# ReflowOwen.net
KiCad netlist of a schematic drawn in Altium Designer
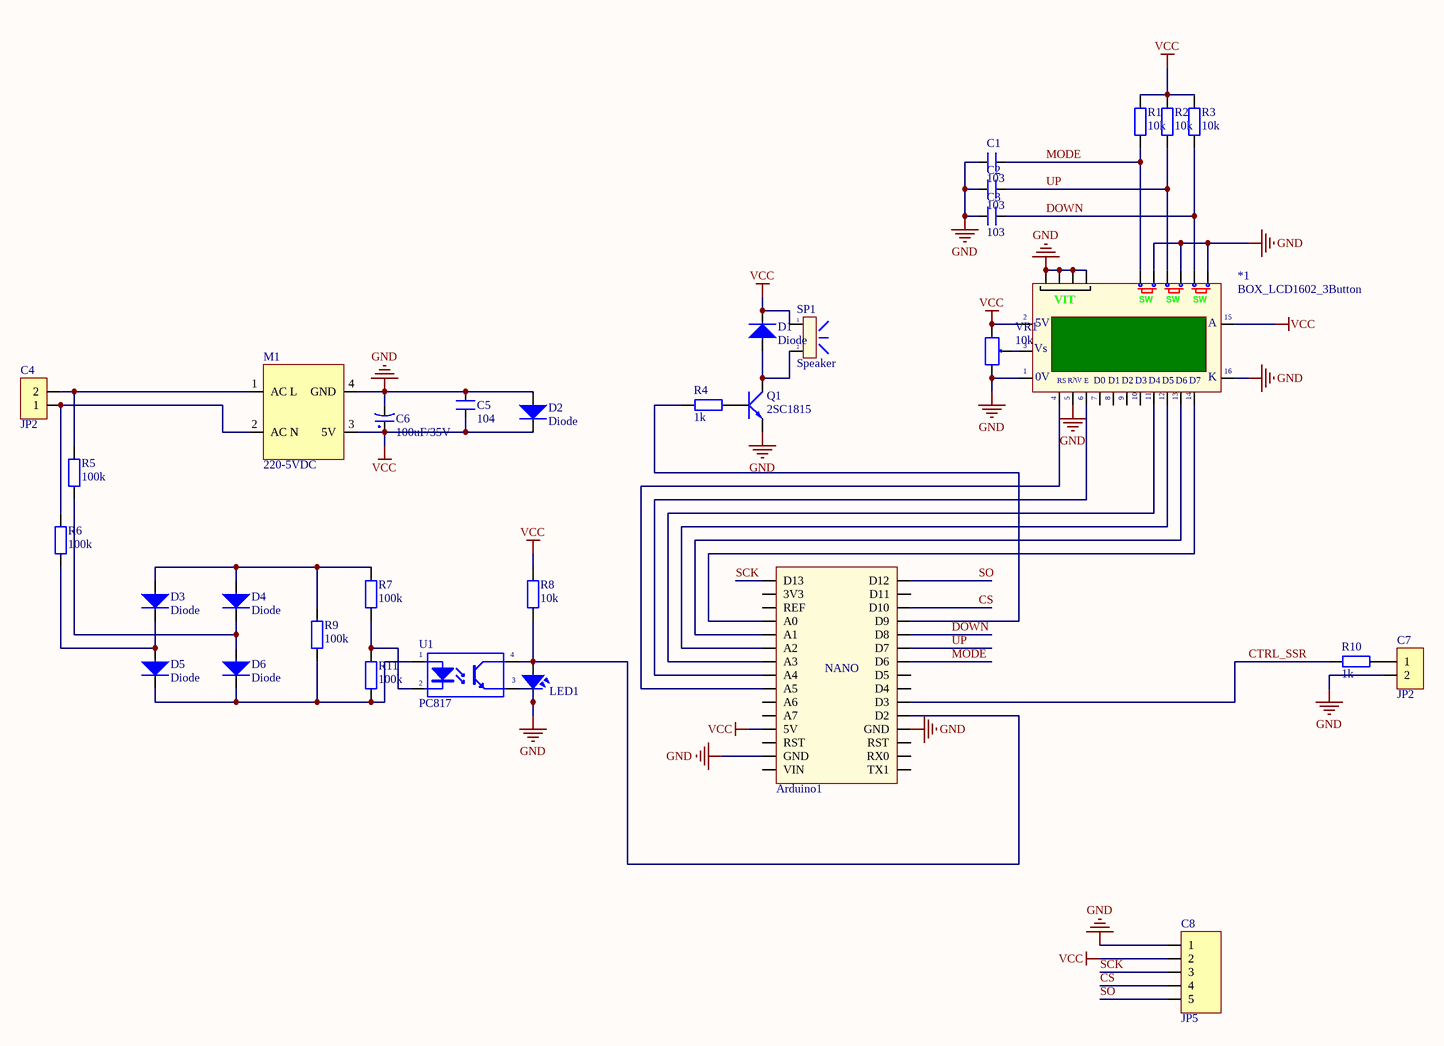
[diagram p0: ReflowOwen.SchDoc]

(export (version "E")
  (design (tool "Eeschema 10.0.6"))
  (components
    (comp (ref "*1")
      (value "BOX_LCD1602_3Button")
      (footprint "BOX_LCD1602_3Button")
      (libsource (lib "OBIT_TESLA") (part "BOX_LCD1602_3Button"))
    )
    (comp (ref "Arduino1")
      (value "Arduino Nano")
      (footprint "Arduino Nano")
      (description "Arduino NANO")
      (libsource (lib "Tesla_Thinh") (part "Arduino Nano"))
    )
    (comp (ref "C1")
      (value "103")
      (footprint "SM-0805")
      (description "Cap SMD")
      (libsource (lib "OBIT_TESLA") (part "CM"))
    )
    (comp (ref "C2")
      (value "103")
      (footprint "SM-0805")
      (description "Cap SMD")
      (libsource (lib "OBIT_TESLA") (part "CM"))
    )
    (comp (ref "C3")
      (value "103")
      (footprint "SM-0805")
      (description "Cap SMD")
      (libsource (lib "OBIT_TESLA") (part "CM"))
    )
    (comp (ref "C4")
      (value "JP2")
      (footprint "JP2-C1T")
      (description "WR-PHD 2.54 mm Angled Socket Header")
      (fields
        (field (name "MANUFACTURER") "Würth Elektronik eiSos GmbH")
        (field (name "PARTNO") "613002143121")
        (field (name "CREATED BY") "Karrer Zheng")
      )
      (libsource (lib "OBIT_TESLA") (part "JP2"))
    )
    (comp (ref "C5")
      (value "104")
      (footprint "CN2")
      (description "Cap np 104 => 105pF")
      (libsource (lib "OBIT_TESLA") (part "CN2"))
    )
    (comp (ref "C6")
      (value "100uF/35V")
      (footprint "CP1.5/3.4")
      (description "Cap 100uF/35V - 470uF/16V")
      (libsource (lib "OBIT_TESLA") (part "CP3"))
    )
    (comp (ref "C7")
      (value "JP2")
      (footprint "JP2-C1T")
      (description "WR-PHD 2.54 mm Angled Socket Header")
      (fields
        (field (name "MANUFACTURER") "Würth Elektronik eiSos GmbH")
        (field (name "PARTNO") "613002143121")
        (field (name "CREATED BY") "Karrer Zheng")
      )
      (libsource (lib "") (part "JP2_1"))
    )
    (comp (ref "C8")
      (value "JP5")
      (footprint "JP5-C1T")
      (description "WR-PHD 2.54 mm Angled Socket Header")
      (fields
        (field (name "MANUFACTURER") "Würth Elektronik eiSos GmbH")
        (field (name "PARTNO") "613005143121")
        (field (name "CREATED BY") "Karrer Zheng")
      )
      (libsource (lib "OBIT_TESLA") (part "JP5"))
    )
    (comp (ref "D1") (value "Diode") (footprint "DIO-SMD-106") (libsource (lib "OBIT_TESLA") (part "Diode")))
    (comp (ref "D2") (value "Diode") (footprint "DIO-SMD-106") (libsource (lib "OBIT_TESLA") (part "Diode")))
    (comp (ref "D3") (value "Diode") (footprint "D1A") (libsource (lib "OBIT_TESLA") (part "Diode")))
    (comp (ref "D4") (value "Diode") (footprint "D1A") (libsource (lib "OBIT_TESLA") (part "Diode")))
    (comp (ref "D5") (value "Diode") (footprint "D1A") (libsource (lib "OBIT_TESLA") (part "Diode")))
    (comp (ref "D6") (value "Diode") (footprint "D1A") (libsource (lib "OBIT_TESLA") (part "Diode")))
    (comp (ref "LED1")
      (value "LED")
      (footprint "LED-5-BLUE")
      (description "LED Single colour Green and Red")
      (libsource (lib "Tesla_Thinh") (part "LED"))
    )
    (comp (ref "M1")
      (value "220-5VDC")
      (footprint "5V 700mA 3.5W AC DC")
      (libsource (lib "OBIT_TESLA") (part "5V 700mA 3.5W AC 220 to DC"))
    )
    (comp (ref "Q1")
      (value "2SC1815")
      (footprint "TO92-123")
      (description "NPN 600mW, ECB")
      (libsource (lib "OBIT_TESLA") (part "2SC1815"))
    )
    (comp (ref "R1")
      (value "10k")
      (footprint "RES-1/4W")
      (description "Resistor R1/4W")
      (libsource (lib "OBIT_TESLA") (part "R"))
    )
    (comp (ref "R2")
      (value "10k")
      (footprint "RES-1/4W")
      (description "Resistor R1/4W")
      (libsource (lib "OBIT_TESLA") (part "R"))
    )
    (comp (ref "R3")
      (value "10k")
      (footprint "RES-1/4W")
      (description "Resistor R1/4W")
      (libsource (lib "OBIT_TESLA") (part "R"))
    )
    (comp (ref "R4")
      (value "1k")
      (footprint "RES-1/4W")
      (description "Resistor R1/4W")
      (libsource (lib "OBIT_TESLA") (part "R"))
    )
    (comp (ref "R5")
      (value "100k")
      (footprint "RES-1/4W")
      (description "Resistor R1/4W")
      (libsource (lib "OBIT_TESLA") (part "R"))
    )
    (comp (ref "R6")
      (value "100k")
      (footprint "RES-1/4W")
      (description "Resistor R1/4W")
      (libsource (lib "OBIT_TESLA") (part "R"))
    )
    (comp (ref "R7")
      (value "100k")
      (footprint "RES-1/4W")
      (description "Resistor R1/4W")
      (libsource (lib "OBIT_TESLA") (part "R"))
    )
    (comp (ref "R8")
      (value "10k")
      (footprint "RES-1/4W")
      (description "Resistor R1/4W")
      (libsource (lib "OBIT_TESLA") (part "R"))
    )
    (comp (ref "R9")
      (value "100k")
      (footprint "RES-1/4W")
      (description "Resistor R1/4W")
      (libsource (lib "OBIT_TESLA") (part "R"))
    )
    (comp (ref "R10")
      (value "1k")
      (footprint "RES-1/4W")
      (description "Resistor R1/4W")
      (libsource (lib "OBIT_TESLA") (part "R"))
    )
    (comp (ref "R11")
      (value "100k")
      (footprint "RES-1/4W")
      (description "Resistor R1/4W")
      (libsource (lib "OBIT_TESLA") (part "R"))
    )
    (comp (ref "SP1")
      (value "Speaker")
      (footprint "SPK")
      (description "Speaker Chip")
      (libsource (lib "OBIT_TESLA") (part "SPK"))
    )
    (comp (ref "U1")
      (value "PC817")
      (footprint "DIP4")
      (description "Single Opto")
      (libsource (lib "Tesla_Thinh") (part "PC817"))
    )
    (comp (ref "VR1") (value "10k") (footprint "VR-S2") (libsource (lib "OBIT_TESLA") (part "Resistor Var")))
  )
  (nets
    (net (code "1") (name "/CS") (class "Default")
      (node (ref "Arduino1") (pin "D10") (pinfunction "D10_D10") (pintype "passive"))
      (node (ref "C8") (pin "4") (pinfunction "4_4") (pintype "passive"))
    )
    (net (code "2") (name "/CTRL_SSR") (class "Default")
      (node (ref "Arduino1") (pin "D3") (pinfunction "D3_D3") (pintype "passive"))
      (node (ref "R10") (pin "1") (pinfunction "1_1") (pintype "passive"))
    )
    (net (code "3") (name "/DOWN") (class "Default")
      (node (ref "*1") (pin "21") (pinfunction "21_21") (pintype "passive"))
      (node (ref "Arduino1") (pin "D8") (pinfunction "D8_D8") (pintype "passive"))
      (node (ref "C3") (pin "2") (pinfunction "2_2") (pintype "passive"))
      (node (ref "R3") (pin "1") (pinfunction "1_1") (pintype "passive"))
    )
    (net (code "4") (name "/MODE") (class "Default")
      (node (ref "*1") (pin "17") (pinfunction "17_17") (pintype "passive"))
      (node (ref "Arduino1") (pin "D6") (pinfunction "D6_D6") (pintype "passive"))
      (node (ref "C1") (pin "2") (pinfunction "2_2") (pintype "passive"))
      (node (ref "R1") (pin "1") (pinfunction "1_1") (pintype "passive"))
    )
    (net (code "5") (name "/SCK") (class "Default")
      (node (ref "Arduino1") (pin "D13") (pinfunction "D13_D13") (pintype "passive"))
      (node (ref "C8") (pin "3") (pinfunction "3_3") (pintype "passive"))
    )
    (net (code "6") (name "/SO") (class "Default")
      (node (ref "Arduino1") (pin "D12") (pinfunction "D12_D12") (pintype "passive"))
      (node (ref "C8") (pin "5") (pinfunction "5_5") (pintype "passive"))
    )
    (net (code "7") (name "/UP") (class "Default")
      (node (ref "*1") (pin "19") (pinfunction "19_19") (pintype "passive"))
      (node (ref "Arduino1") (pin "D7") (pinfunction "D7_D7") (pintype "passive"))
      (node (ref "C2") (pin "2") (pinfunction "2_2") (pintype "passive"))
      (node (ref "R2") (pin "1") (pinfunction "1_1") (pintype "passive"))
    )
    (net (code "8") (name "GND") (class "Default")
      (node (ref "*1") (pin "1") (pinfunction "GND_1") (pintype "passive"))
      (node (ref "*1") (pin "16") (pinfunction "K_16") (pintype "passive"))
      (node (ref "*1") (pin "18") (pinfunction "18_18") (pintype "passive"))
      (node (ref "*1") (pin "20") (pinfunction "20_20") (pintype "passive"))
      (node (ref "*1") (pin "22") (pinfunction "22_22") (pintype "passive"))
      (node (ref "*1") (pin "23") (pinfunction "23_23") (pintype "passive"))
      (node (ref "*1") (pin "24") (pinfunction "24_24") (pintype "passive"))
      (node (ref "*1") (pin "25") (pinfunction "25_25") (pintype "passive"))
      (node (ref "*1") (pin "26") (pinfunction "26_26") (pintype "passive"))
      (node (ref "*1") (pin "5") (pinfunction "R/~{W}_5") (pintype "passive"))
      (node (ref "Arduino1") (pin "GND") (pinfunction "GND_GND") (pintype "passive"))
      (node (ref "C1") (pin "1") (pinfunction "1_1") (pintype "passive"))
      (node (ref "C2") (pin "1") (pinfunction "1_1") (pintype "passive"))
      (node (ref "C3") (pin "1") (pinfunction "1_1") (pintype "passive"))
      (node (ref "C5") (pin "2") (pinfunction "2_2") (pintype "passive"))
      (node (ref "C6") (pin "2") (pinfunction "2_2") (pintype "passive"))
      (node (ref "C7") (pin "2") (pinfunction "2_2") (pintype "passive"))
      (node (ref "C8") (pin "1") (pinfunction "1_1") (pintype "passive"))
      (node (ref "D2") (pin "1") (pinfunction "1_1") (pintype "passive"))
      (node (ref "LED1") (pin "2") (pinfunction "2_2") (pintype "passive"))
      (node (ref "M1") (pin "4") (pinfunction "GND_4") (pintype "passive"))
      (node (ref "Q1") (pin "1") (pinfunction "E_1") (pintype "passive"))
      (node (ref "U1") (pin "3") (pinfunction "E_3") (pintype "passive"))
      (node (ref "VR1") (pin "3") (pinfunction "3_3") (pintype "passive"))
    )
    (net (code "9") (name "Net-(*1-D4)") (class "Default")
      (node (ref "*1") (pin "11") (pinfunction "D4_11") (pintype "passive"))
      (node (ref "Arduino1") (pin "A3") (pinfunction "A3_A3") (pintype "passive"))
    )
    (net (code "10") (name "Net-(*1-D5)") (class "Default")
      (node (ref "*1") (pin "12") (pinfunction "D5_12") (pintype "passive"))
      (node (ref "Arduino1") (pin "A2") (pinfunction "A2_A2") (pintype "passive"))
    )
    (net (code "11") (name "Net-(*1-D6)") (class "Default")
      (node (ref "*1") (pin "13") (pinfunction "D6_13") (pintype "passive"))
      (node (ref "Arduino1") (pin "A1") (pinfunction "A1_A1") (pintype "passive"))
    )
    (net (code "12") (name "Net-(*1-D7)") (class "Default")
      (node (ref "*1") (pin "14") (pinfunction "D7_14") (pintype "passive"))
      (node (ref "Arduino1") (pin "A0") (pinfunction "A0_A0") (pintype "passive"))
    )
    (net (code "13") (name "Net-(*1-RS)") (class "Default")
      (node (ref "*1") (pin "4") (pinfunction "RS_4") (pintype "passive"))
      (node (ref "Arduino1") (pin "A5") (pinfunction "A5_A5") (pintype "passive"))
    )
    (net (code "14") (name "Net-(*1-VEE)") (class "Default")
      (node (ref "*1") (pin "3") (pinfunction "VEE_3") (pintype "passive"))
      (node (ref "VR1") (pin "2") (pinfunction "2_2") (pintype "passive"))
    )
    (net (code "15") (name "Net-(*1-~{EN})") (class "Default")
      (node (ref "*1") (pin "6") (pinfunction "~{EN}_6") (pintype "passive"))
      (node (ref "Arduino1") (pin "A4") (pinfunction "A4_A4") (pintype "passive"))
    )
    (net (code "16") (name "Net-(Arduino1-PadD9)") (class "Default")
      (node (ref "Arduino1") (pin "D9") (pinfunction "D9_D9") (pintype "passive"))
      (node (ref "R4") (pin "1") (pinfunction "1_1") (pintype "passive"))
    )
    (net (code "17") (name "Net-(C7-Pad1)") (class "Default")
      (node (ref "C7") (pin "1") (pinfunction "1_1") (pintype "passive"))
      (node (ref "R10") (pin "2") (pinfunction "2_2") (pintype "passive"))
    )
    (net (code "18") (name "Net-(D3-Pad1)") (class "Default")
      (node (ref "D3") (pin "1") (pinfunction "1_1") (pintype "passive"))
      (node (ref "D4") (pin "1") (pinfunction "1_1") (pintype "passive"))
      (node (ref "R7") (pin "2") (pinfunction "2_2") (pintype "passive"))
      (node (ref "R9") (pin "2") (pinfunction "2_2") (pintype "passive"))
    )
    (net (code "19") (name "Net-(D3-Pad2)") (class "Default")
      (node (ref "D3") (pin "2") (pinfunction "2_2") (pintype "passive"))
      (node (ref "D5") (pin "1") (pinfunction "1_1") (pintype "passive"))
      (node (ref "R6") (pin "1") (pinfunction "1_1") (pintype "passive"))
    )
    (net (code "20") (name "Net-(D4-Pad2)") (class "Default")
      (node (ref "D4") (pin "2") (pinfunction "2_2") (pintype "passive"))
      (node (ref "D6") (pin "1") (pinfunction "1_1") (pintype "passive"))
      (node (ref "R5") (pin "1") (pinfunction "1_1") (pintype "passive"))
    )
    (net (code "21") (name "Net-(M1-AC_L)") (class "Default")
      (node (ref "C4") (pin "2") (pinfunction "2_2") (pintype "passive"))
      (node (ref "M1") (pin "1") (pinfunction "AC_L_1") (pintype "passive"))
      (node (ref "R5") (pin "2") (pinfunction "2_2") (pintype "passive"))
    )
    (net (code "22") (name "Net-(M1-AC_N)") (class "Default")
      (node (ref "C4") (pin "1") (pinfunction "1_1") (pintype "passive"))
      (node (ref "M1") (pin "2") (pinfunction "AC_N_2") (pintype "passive"))
      (node (ref "R6") (pin "2") (pinfunction "2_2") (pintype "passive"))
    )
    (net (code "23") (name "Net-(Q1-B)") (class "Default")
      (node (ref "Q1") (pin "3") (pinfunction "B_3") (pintype "passive"))
      (node (ref "R4") (pin "2") (pinfunction "2_2") (pintype "passive"))
    )
    (net (code "24") (name "Net-(Q1-C)") (class "Default")
      (node (ref "D1") (pin "1") (pinfunction "1_1") (pintype "passive"))
      (node (ref "Q1") (pin "2") (pinfunction "C_2") (pintype "passive"))
      (node (ref "SP1") (pin "2") (pinfunction "2_2") (pintype "passive"))
    )
    (net (code "25") (name "Net-(U1-A)") (class "Default")
      (node (ref "D5") (pin "2") (pinfunction "2_2") (pintype "passive"))
      (node (ref "D6") (pin "2") (pinfunction "2_2") (pintype "passive"))
      (node (ref "R11") (pin "1") (pinfunction "1_1") (pintype "passive"))
      (node (ref "R9") (pin "1") (pinfunction "1_1") (pintype "passive"))
      (node (ref "U1") (pin "1") (pinfunction "A_1") (pintype "passive"))
    )
    (net (code "26") (name "Net-(U1-C)") (class "Default")
      (node (ref "Arduino1") (pin "D2") (pinfunction "D2_D2") (pintype "passive"))
      (node (ref "LED1") (pin "1") (pinfunction "1_1") (pintype "passive"))
      (node (ref "R8") (pin "1") (pinfunction "1_1") (pintype "passive"))
      (node (ref "U1") (pin "4") (pinfunction "C_4") (pintype "passive"))
    )
    (net (code "27") (name "Net-(U1-K)") (class "Default")
      (node (ref "R11") (pin "2") (pinfunction "2_2") (pintype "passive"))
      (node (ref "R7") (pin "1") (pinfunction "1_1") (pintype "passive"))
      (node (ref "U1") (pin "2") (pinfunction "K_2") (pintype "passive"))
    )
    (net (code "28") (name "VCC") (class "Default")
      (node (ref "*1") (pin "15") (pinfunction "A_15") (pintype "passive"))
      (node (ref "*1") (pin "2") (pinfunction "VDD_2") (pintype "passive"))
      (node (ref "Arduino1") (pin "5V") (pinfunction "5V_5V") (pintype "passive"))
      (node (ref "C5") (pin "1") (pinfunction "1_1") (pintype "passive"))
      (node (ref "C6") (pin "1") (pinfunction "1_1") (pintype "passive"))
      (node (ref "C8") (pin "2") (pinfunction "2_2") (pintype "passive"))
      (node (ref "D1") (pin "2") (pinfunction "2_2") (pintype "passive"))
      (node (ref "D2") (pin "2") (pinfunction "2_2") (pintype "passive"))
      (node (ref "M1") (pin "3") (pinfunction "5V_3") (pintype "passive"))
      (node (ref "R1") (pin "2") (pinfunction "2_2") (pintype "passive"))
      (node (ref "R2") (pin "2") (pinfunction "2_2") (pintype "passive"))
      (node (ref "R3") (pin "2") (pinfunction "2_2") (pintype "passive"))
      (node (ref "R8") (pin "2") (pinfunction "2_2") (pintype "passive"))
      (node (ref "SP1") (pin "1") (pinfunction "1_1") (pintype "passive"))
      (node (ref "VR1") (pin "1") (pinfunction "1_1") (pintype "passive"))
    )
    (net (code "29") (name "unconnected-(*1-D0-Pad7)") (class "Default")
      (node (ref "*1") (pin "7") (pinfunction "D0_7") (pintype "passive"))
    )
    (net (code "30") (name "unconnected-(*1-D1-Pad8)") (class "Default")
      (node (ref "*1") (pin "8") (pinfunction "D1_8") (pintype "passive"))
    )
    (net (code "31") (name "unconnected-(*1-D2-Pad9)") (class "Default")
      (node (ref "*1") (pin "9") (pinfunction "D2_9") (pintype "passive"))
    )
    (net (code "32") (name "unconnected-(*1-D3-Pad10)") (class "Default")
      (node (ref "*1") (pin "10") (pinfunction "D3_10") (pintype "passive"))
    )
    (net (code "33") (name "unconnected-(Arduino1-Pad3V3)") (class "Default")
      (node (ref "Arduino1") (pin "3V3") (pinfunction "3V3_3V3") (pintype "passive"))
    )
    (net (code "34") (name "unconnected-(Arduino1-PadA6)") (class "Default")
      (node (ref "Arduino1") (pin "A6") (pinfunction "A6_A6") (pintype "passive"))
    )
    (net (code "35") (name "unconnected-(Arduino1-PadA7)") (class "Default")
      (node (ref "Arduino1") (pin "A7") (pinfunction "A7_A7") (pintype "passive"))
    )
    (net (code "36") (name "unconnected-(Arduino1-PadD4)") (class "Default")
      (node (ref "Arduino1") (pin "D4") (pinfunction "D4_D4") (pintype "passive"))
    )
    (net (code "37") (name "unconnected-(Arduino1-PadD5)") (class "Default")
      (node (ref "Arduino1") (pin "D5") (pinfunction "D5_D5") (pintype "passive"))
    )
    (net (code "38") (name "unconnected-(Arduino1-PadD11)") (class "Default")
      (node (ref "Arduino1") (pin "D11") (pinfunction "D11_D11") (pintype "passive"))
    )
    (net (code "39") (name "unconnected-(Arduino1-PadREF)") (class "Default")
      (node (ref "Arduino1") (pin "REF") (pinfunction "REF_REF") (pintype "passive"))
    )
    (net (code "40") (name "unconnected-(Arduino1-PadRST)") (class "Default")
      (node (ref "Arduino1") (pin "RST") (pinfunction "RST_RST") (pintype "passive"))
    )
    (net (code "41") (name "unconnected-(Arduino1-PadRST)_1") (class "Default")
      (node (ref "Arduino1") (pin "RST") (pinfunction "RST_RST") (pintype "passive"))
    )
    (net (code "42") (name "unconnected-(Arduino1-PadRX0)") (class "Default")
      (node (ref "Arduino1") (pin "RX0") (pinfunction "RX0_RX0") (pintype "passive"))
    )
    (net (code "43") (name "unconnected-(Arduino1-PadTX1)") (class "Default")
      (node (ref "Arduino1") (pin "TX1") (pinfunction "TX1_TX1") (pintype "passive"))
    )
    (net (code "44") (name "unconnected-(Arduino1-PadVIN)") (class "Default")
      (node (ref "Arduino1") (pin "VIN") (pinfunction "VIN_VIN") (pintype "passive"))
    )
  )
)
